# RS485.net
KiCad netlist of a schematic drawn in Altium Designer
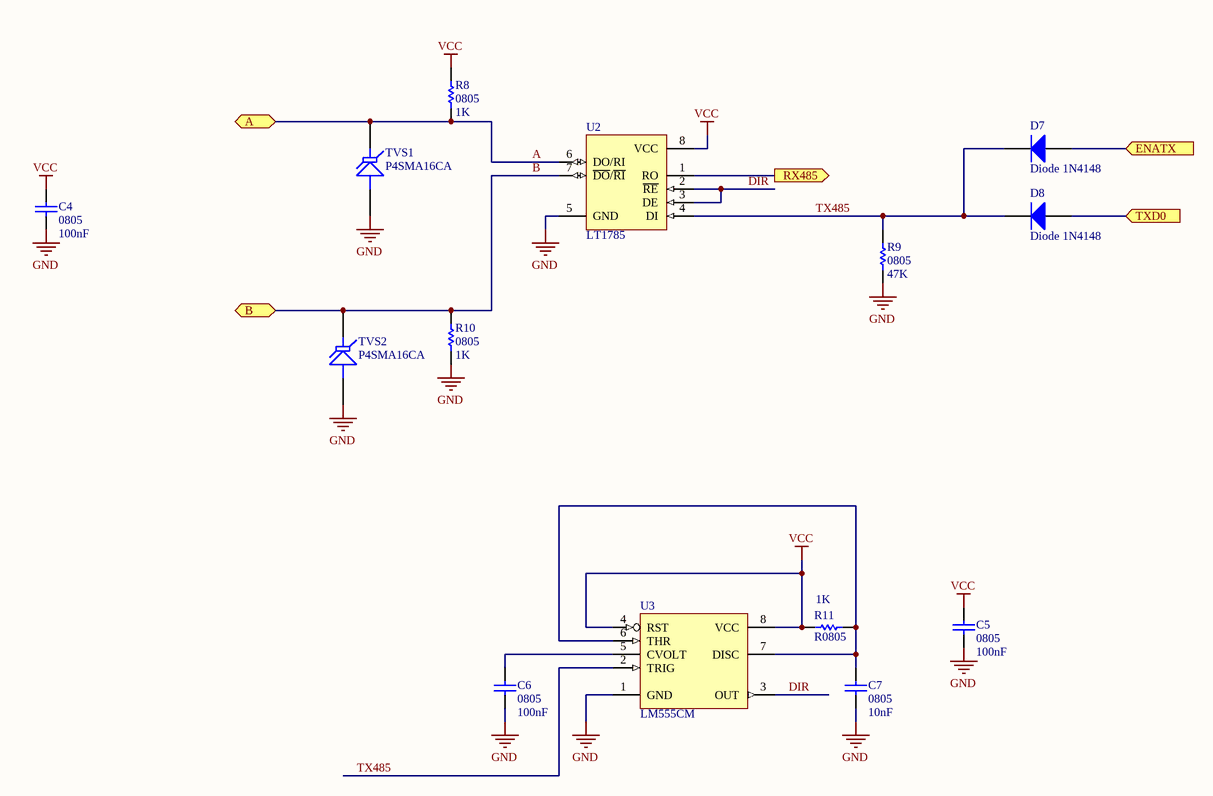
[diagram p0: RS485.SchDoc]

(export (version "E")
  (design (tool "Eeschema 10.0.6"))
  (components
    (comp (ref "C4")
      (value "0805")
      (footprint "C0805C")
      (description "Cap 100nF 25V X7R")
      (fields
        (field (name "ALTIUM_VALUE") "100nF")
        (field (name "PART") "399-1170-1-ND")
        (field (name "PUBLISHER") "Altium Limited")
      )
      (libsource (lib "PROPIASchlib") (part "Cap 0805"))
    )
    (comp (ref "C5")
      (value "0805")
      (footprint "C0805C")
      (description "Cap 100nF 25V X7R")
      (fields
        (field (name "ALTIUM_VALUE") "100nF")
        (field (name "PART") "399-1170-1-ND")
        (field (name "PUBLISHER") "Altium Limited")
      )
      (libsource (lib "PROPIASchlib") (part "Cap 0805"))
    )
    (comp (ref "C6")
      (value "0805")
      (footprint "C0805C")
      (description "Cap 100nF 25V X7R")
      (fields
        (field (name "PART") "399-1170-1-ND")
        (field (name "ALTIUM_VALUE") "100nF")
        (field (name "PUBLISHER") "Altium Limited")
      )
      (libsource (lib "PROPIASchlib") (part "Cap 0805"))
    )
    (comp (ref "C7")
      (value "0805")
      (footprint "C0805C")
      (description "Cap 100nF 25V X7R")
      (fields
        (field (name "PART") "399-1158-1-ND")
        (field (name "ALTIUM_VALUE") "10nF")
        (field (name "PUBLISHER") "Altium Limited")
      )
      (libsource (lib "PROPIASchlib") (part "Cap 0805 10nF"))
    )
    (comp (ref "D7")
      (value "Diode 1N4148")
      (footprint "1N4148SMD")
      (description "1N4148")
      (fields (field (name "PART") "1N4148WTPMSCT") (field (name "PUBLISHER") "Altium Limited"))
      (libsource (lib "PROPIASchlib") (part "Diode 1N4148"))
    )
    (comp (ref "D8")
      (value "Diode 1N4148")
      (footprint "1N4148SMD")
      (description "1N4148")
      (fields (field (name "PART") "1N4148WTPMSCT") (field (name "PUBLISHER") "Altium Limited"))
      (libsource (lib "PROPIASchlib") (part "Diode 1N4148"))
    )
    (comp (ref "R8")
      (value "0805")
      (footprint "R0805")
      (description "Semiconductor Resistor")
      (fields
        (field (name "PART") "541-1.0KACT")
        (field (name "ALTIUM_VALUE") "1K")
        (field (name "PUBLISHER") "Altium Limited")
      )
      (libsource (lib "PROPIASchlib") (part "Res 0805 1K"))
    )
    (comp (ref "R9")
      (value "0805")
      (footprint "R0805")
      (description "Semiconductor Resistor")
      (fields
        (field (name "PART") "541-47KACT")
        (field (name "ALTIUM_VALUE") "47K")
        (field (name "PUBLISHER") "Altium Limited")
      )
      (libsource (lib "PROPIASchlib") (part "Res 0805 47K"))
    )
    (comp (ref "R10")
      (value "0805")
      (footprint "R0805")
      (description "Semiconductor Resistor")
      (fields
        (field (name "PART") "541-1.0KACT")
        (field (name "ALTIUM_VALUE") "1K")
        (field (name "PUBLISHER") "Altium Limited")
      )
      (libsource (lib "PROPIASchlib") (part "Res 0805 1K"))
    )
    (comp (ref "R11")
      (value "R0805")
      (footprint "R0805")
      (description "Semiconductor Resistor")
      (fields
        (field (name "PART") "311-1.0KARCT-ND")
        (field (name "ALTIUM_VALUE") "1K")
        (field (name "PUBLISHER") "Altium Limited")
      )
      (libsource (lib "PROPIASchlib") (part "Res 0805 1K"))
    )
    (comp (ref "TVS1")
      (value "P4SMA16CA")
      (footprint "TVS")
      (description "Tranzorb")
      (fields (field (name "PART") "P4SMA16CA-ND") (field (name "PUBLISHER") "Altium Limited"))
      (libsource (lib "PROPIASchlib") (part "Tranzorb"))
    )
    (comp (ref "TVS2")
      (value "P4SMA16CA")
      (footprint "TVS")
      (description "Tranzorb")
      (fields (field (name "PART") "P4SMA16CA-ND") (field (name "PUBLISHER") "Altium Limited"))
      (libsource (lib "PROPIASchlib") (part "Tranzorb"))
    )
    (comp (ref "U2")
      (value "LT1785")
      (footprint "M08A_N")
      (description "IC TXRX RS485/RS422 60V 8-SOIC")
      (fields (field (name "PART") "LT1785IS8#PBF") (field (name "PUBLISHER") "Altium Limited"))
      (libsource (lib "PROPIASchlib") (part "LT1785"))
    )
    (comp (ref "U3")
      (value "LM555CM")
      (footprint "M08A_N")
      (description "Timer")
      (fields (field (name "PUBLISHER") "Altium Limited"))
      (libsource (lib "NSC Analog Timer Circuit") (part "LM555CM"))
    )
  )
  (nets
    (net (code "1") (name "/A") (class "Default")
      (node (ref "R8") (pin "1") (pinfunction "1_1") (pintype "passive"))
      (node (ref "TVS1") (pin "2") (pinfunction "K_2") (pintype "passive"))
      (node (ref "U2") (pin "6") (pinfunction "DO/RI_6") (pintype "bidirectional"))
    )
    (net (code "2") (name "/B") (class "Default")
      (node (ref "R10") (pin "2") (pinfunction "2_2") (pintype "passive"))
      (node (ref "TVS2") (pin "2") (pinfunction "K_2") (pintype "passive"))
      (node (ref "U2") (pin "7") (pinfunction "~{DO}/~{RI}_7") (pintype "bidirectional"))
    )
    (net (code "3") (name "/DIR") (class "Default")
      (node (ref "U2") (pin "2") (pinfunction "~{RE}_2") (pintype "input"))
      (node (ref "U2") (pin "3") (pinfunction "DE_3") (pintype "input"))
      (node (ref "U3") (pin "3") (pinfunction "OUT_3") (pintype "output"))
    )
    (net (code "4") (name "/ENATX") (class "Default")
      (node (ref "D7") (pin "1") (pinfunction "A_1") (pintype "passive"))
    )
    (net (code "5") (name "/RX485") (class "Default")
      (node (ref "U2") (pin "1") (pinfunction "RO_1") (pintype "tri_state"))
    )
    (net (code "6") (name "/TX485") (class "Default")
      (node (ref "D7") (pin "2") (pinfunction "K_2") (pintype "passive"))
      (node (ref "D8") (pin "2") (pinfunction "K_2") (pintype "passive"))
      (node (ref "R9") (pin "2") (pinfunction "2_2") (pintype "passive"))
      (node (ref "U2") (pin "4") (pinfunction "DI_4") (pintype "input"))
      (node (ref "U3") (pin "2") (pinfunction "TRIG_2") (pintype "input"))
    )
    (net (code "7") (name "/TXD0") (class "Default")
      (node (ref "D8") (pin "1") (pinfunction "A_1") (pintype "passive"))
    )
    (net (code "8") (name "GND") (class "Default")
      (node (ref "C4") (pin "1") (pinfunction "1_1") (pintype "passive"))
      (node (ref "C5") (pin "1") (pinfunction "1_1") (pintype "passive"))
      (node (ref "C6") (pin "1") (pinfunction "1_1") (pintype "passive"))
      (node (ref "C7") (pin "1") (pinfunction "1_1") (pintype "passive"))
      (node (ref "R10") (pin "1") (pinfunction "1_1") (pintype "passive"))
      (node (ref "R9") (pin "1") (pinfunction "1_1") (pintype "passive"))
      (node (ref "TVS1") (pin "1") (pinfunction "A_1") (pintype "passive"))
      (node (ref "TVS2") (pin "1") (pinfunction "A_1") (pintype "passive"))
      (node (ref "U2") (pin "5") (pinfunction "GND_5") (pintype "power_in"))
      (node (ref "U3") (pin "1") (pinfunction "GND_1") (pintype "power_in"))
    )
    (net (code "9") (name "Net-(U3-CVOLT)") (class "Default")
      (node (ref "C6") (pin "2") (pinfunction "2_2") (pintype "passive"))
      (node (ref "U3") (pin "5") (pinfunction "CVOLT_5") (pintype "passive"))
    )
    (net (code "10") (name "Net-(U3-DISC)") (class "Default")
      (node (ref "C7") (pin "2") (pinfunction "2_2") (pintype "passive"))
      (node (ref "R11") (pin "2") (pinfunction "2_2") (pintype "passive"))
      (node (ref "U3") (pin "6") (pinfunction "THR_6") (pintype "input"))
      (node (ref "U3") (pin "7") (pinfunction "DISC_7") (pintype "open_collector"))
    )
    (net (code "11") (name "VCC") (class "Default")
      (node (ref "C4") (pin "2") (pinfunction "2_2") (pintype "passive"))
      (node (ref "C5") (pin "2") (pinfunction "2_2") (pintype "passive"))
      (node (ref "R11") (pin "1") (pinfunction "1_1") (pintype "passive"))
      (node (ref "R8") (pin "2") (pinfunction "2_2") (pintype "passive"))
      (node (ref "U2") (pin "8") (pinfunction "VCC_8") (pintype "power_in"))
      (node (ref "U3") (pin "4") (pinfunction "RST_4") (pintype "input"))
      (node (ref "U3") (pin "8") (pinfunction "VCC_8") (pintype "power_in"))
    )
  )
)
